# brick_analog_touch.net
KiCad netlist of a schematic drawn in EAGLE
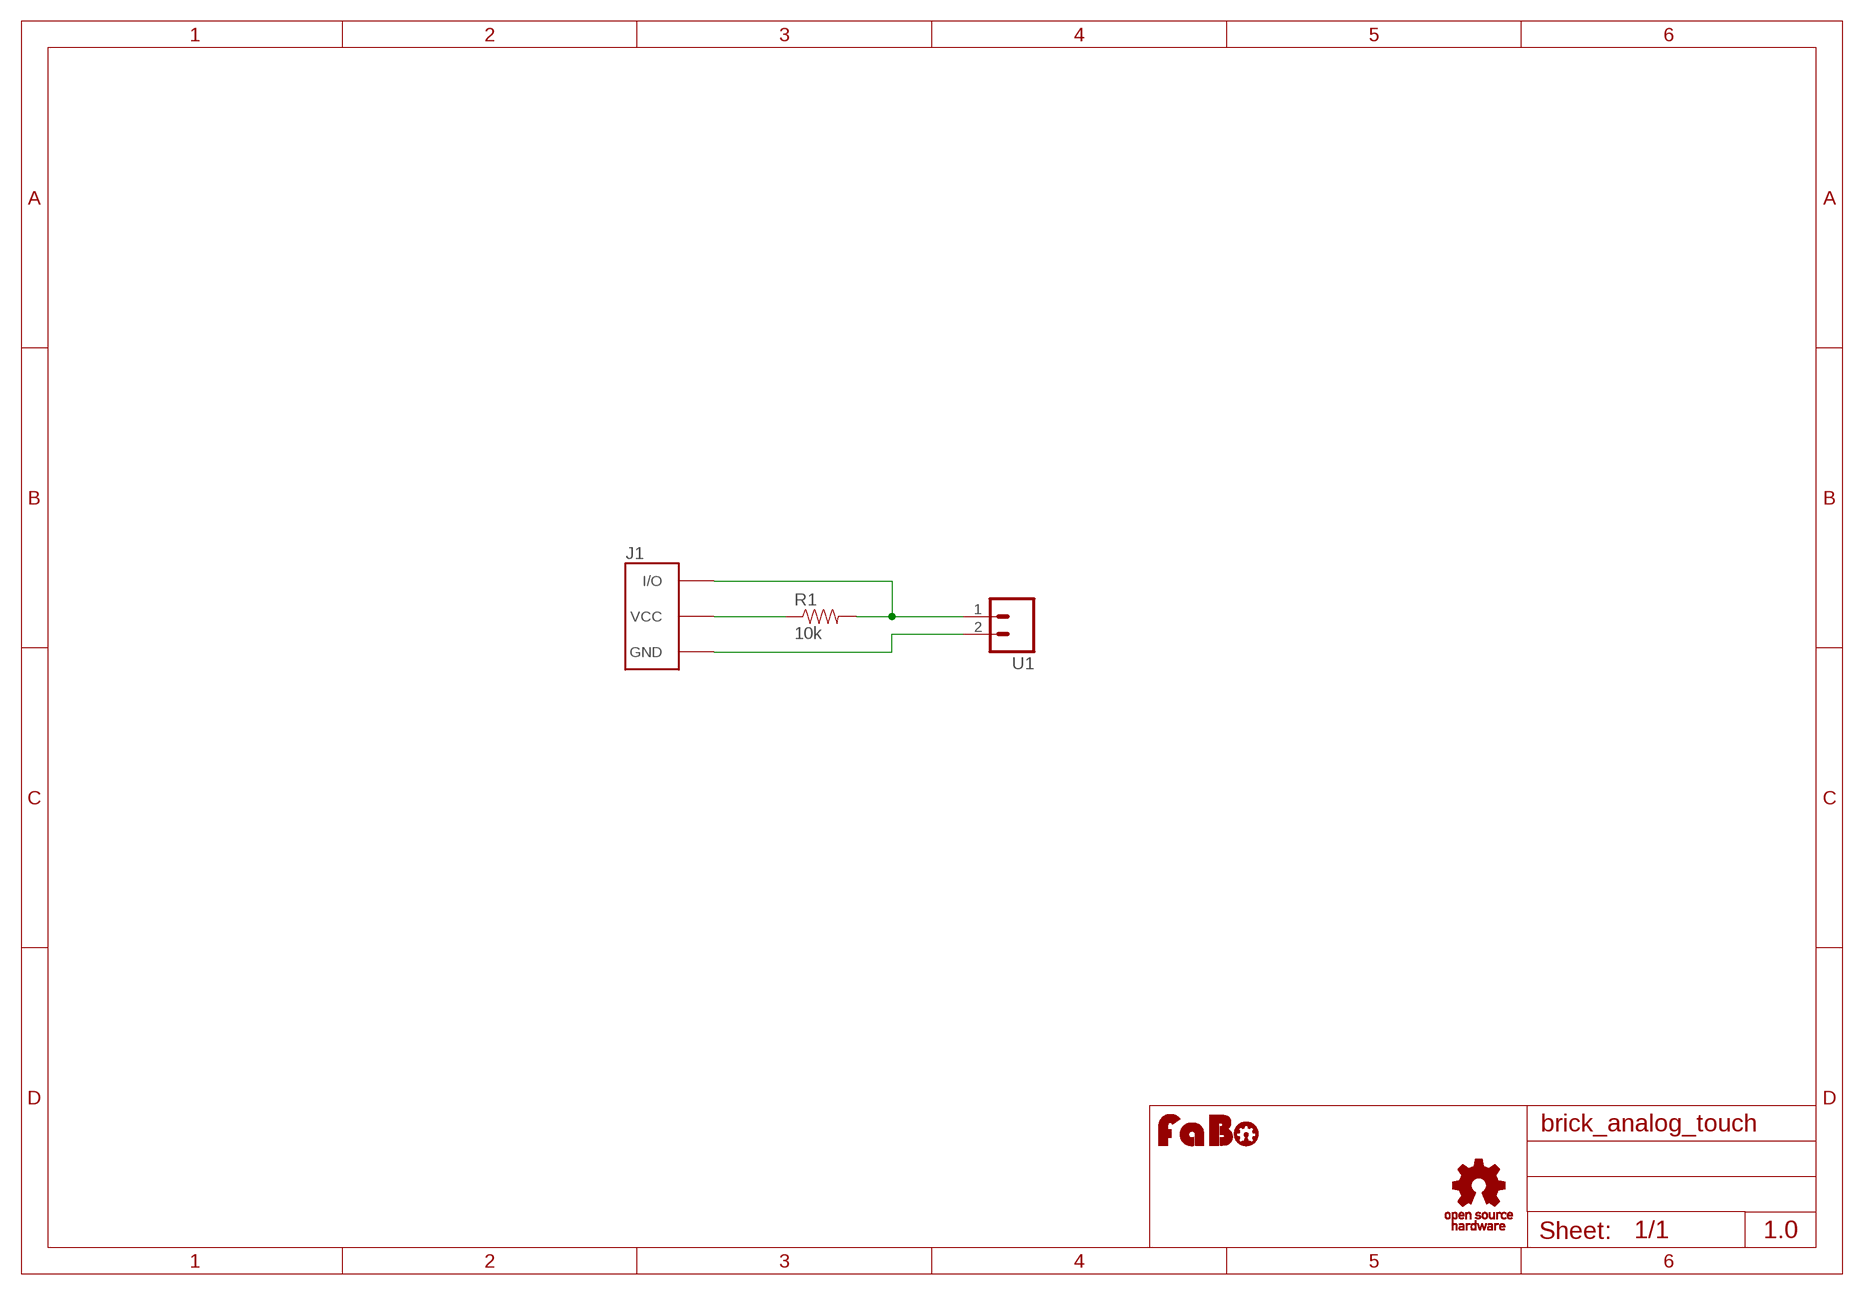
[diagram p0: schematic, sheet 1]

(export (version "E")
  (design (tool "Eeschema 10.0.6"))
  (components
    (comp (ref "J1")
      (value "BRICK_3PIN_NORMAL")
      (footprint "eagle-import:BRICK_3PIN")
      (libsource (lib "eagle-import") (part "BRICK_3PIN_NORMAL"))
    )
    (comp (ref "R1")
      (value "10k")
      (footprint "eagle-import:RES-AXL-REGULAR")
      (libsource (lib "eagle-import") (part "RES-PTH-REGULAR"))
    )
    (comp (ref "U$2")
      (value "LOGO_OSHW_T-M")
      (footprint "eagle-import:LOGO_OSHW_T_M")
      (libsource (lib "eagle-import") (part "LOGO_OSHW_T-M"))
    )
    (comp (ref "U$3")
      (value "LOGO_FABO-M")
      (footprint "eagle-import:LOGO_FABO_M")
      (libsource (lib "eagle-import") (part "LOGO_FABO-M"))
    )
    (comp (ref "U1")
      (value "M02LOCK")
      (footprint "eagle-import:1X02_LOCK")
      (libsource (lib "eagle-import") (part "M02LOCK"))
    )
  )
  (nets
    (net (code "1") (name "Net-(J1-I{slash}O)") (class "Default")
      (node (ref "J1") (pin "IN/OUT") (pinfunction "I/O_IN/OUT") (pintype "bidirectional"))
      (node (ref "R1") (pin "P$2") (pinfunction "2_P$2") (pintype "passive"))
      (node (ref "U1") (pin "1") (pinfunction "1_1") (pintype "passive"))
    )
    (net (code "2") (name "Net-(J1-PadGND)") (class "Default")
      (node (ref "J1") (pin "GND") (pinfunction "GND_GND") (pintype "bidirectional"))
      (node (ref "U1") (pin "2") (pinfunction "2_2") (pintype "passive"))
    )
    (net (code "3") (name "Net-(R1-1)") (class "Default")
      (node (ref "J1") (pin "VCC") (pinfunction "VCC_VCC") (pintype "bidirectional"))
      (node (ref "R1") (pin "P$1") (pinfunction "1_P$1") (pintype "passive"))
    )
  )
)
